# 18_HD4_PUMP_2.net
KiCad netlist of a schematic drawn in Altium Designer
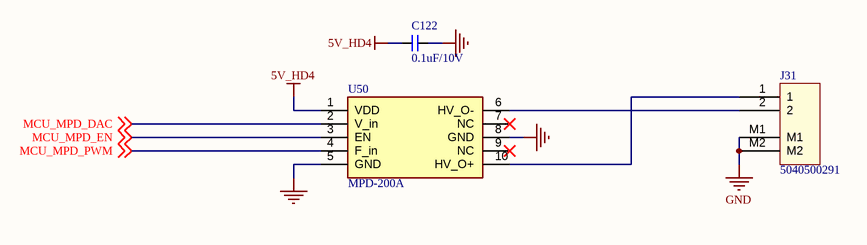
[diagram p0: 18_HD4_PUMP_2.SchDoc]

(export (version "E")
  (design (tool "Eeschema 10.0.6"))
  (components
    (comp (ref "C122")
      (value "0.1uF/10V")
      (footprint "CAP_C_1005X50_L")
      (description "CAP")
      (libsource (lib "LABLIB") (part "_CAP_C_2"))
    )
    (comp (ref "J31")
      (value "5040500291")
      (footprint "MOLEX_5040500291")
      (libsource (lib "LABLIB") (part "Header 2x1_2M"))
    )
    (comp (ref "U50") (value "MPD-200A") (footprint "MPD-200a") (libsource (lib "LABLIB") (part "MPD-200A")))
  )
  (nets
    (net (code "1") (name "5V_HD4") (class "Default")
      (node (ref "C122") (pin "2") (pinfunction "2_2") (pintype "passive"))
      (node (ref "U50") (pin "1") (pinfunction "VDD_1") (pintype "passive"))
    )
    (net (code "2") (name "GND") (class "Default")
      (node (ref "C122") (pin "1") (pinfunction "1_1") (pintype "passive"))
      (node (ref "J31") (pin "M1") (pinfunction "M1_M1") (pintype "passive"))
      (node (ref "J31") (pin "M2") (pinfunction "M2_M2") (pintype "passive"))
      (node (ref "U50") (pin "5") (pinfunction "GND_5") (pintype "passive"))
      (node (ref "U50") (pin "8") (pinfunction "GND_8") (pintype "passive"))
    )
    (net (code "3") (name "MCU_MPD_DAC") (class "Default")
      (node (ref "U50") (pin "2") (pinfunction "V_in_2") (pintype "passive"))
    )
    (net (code "4") (name "MCU_MPD_EN") (class "Default")
      (node (ref "U50") (pin "3") (pinfunction "EN_3") (pintype "passive"))
    )
    (net (code "5") (name "MCU_MPD_PWM") (class "Default")
      (node (ref "U50") (pin "4") (pinfunction "F_in_4") (pintype "passive"))
    )
    (net (code "6") (name "Net-(U50-HV_O+)") (class "Default")
      (node (ref "J31") (pin "1") (pinfunction "1_1") (pintype "passive"))
      (node (ref "U50") (pin "10") (pinfunction "HV_O+_10") (pintype "passive"))
    )
    (net (code "7") (name "Net-(U50-HV_O-)") (class "Default")
      (node (ref "J31") (pin "2") (pinfunction "2_2") (pintype "passive"))
      (node (ref "U50") (pin "6") (pinfunction "HV_O-_6") (pintype "passive"))
    )
    (net (code "8") (name "unconnected-(U50-NC-Pad7)") (class "Default")
      (node (ref "U50") (pin "7") (pinfunction "NC_7") (pintype "passive+no_connect"))
    )
    (net (code "9") (name "unconnected-(U50-NC-Pad9)") (class "Default")
      (node (ref "U50") (pin "9") (pinfunction "NC_9") (pintype "passive+no_connect"))
    )
  )
)
